# robot_secondaire.net
KiCad netlist of a schematic drawn in EAGLE
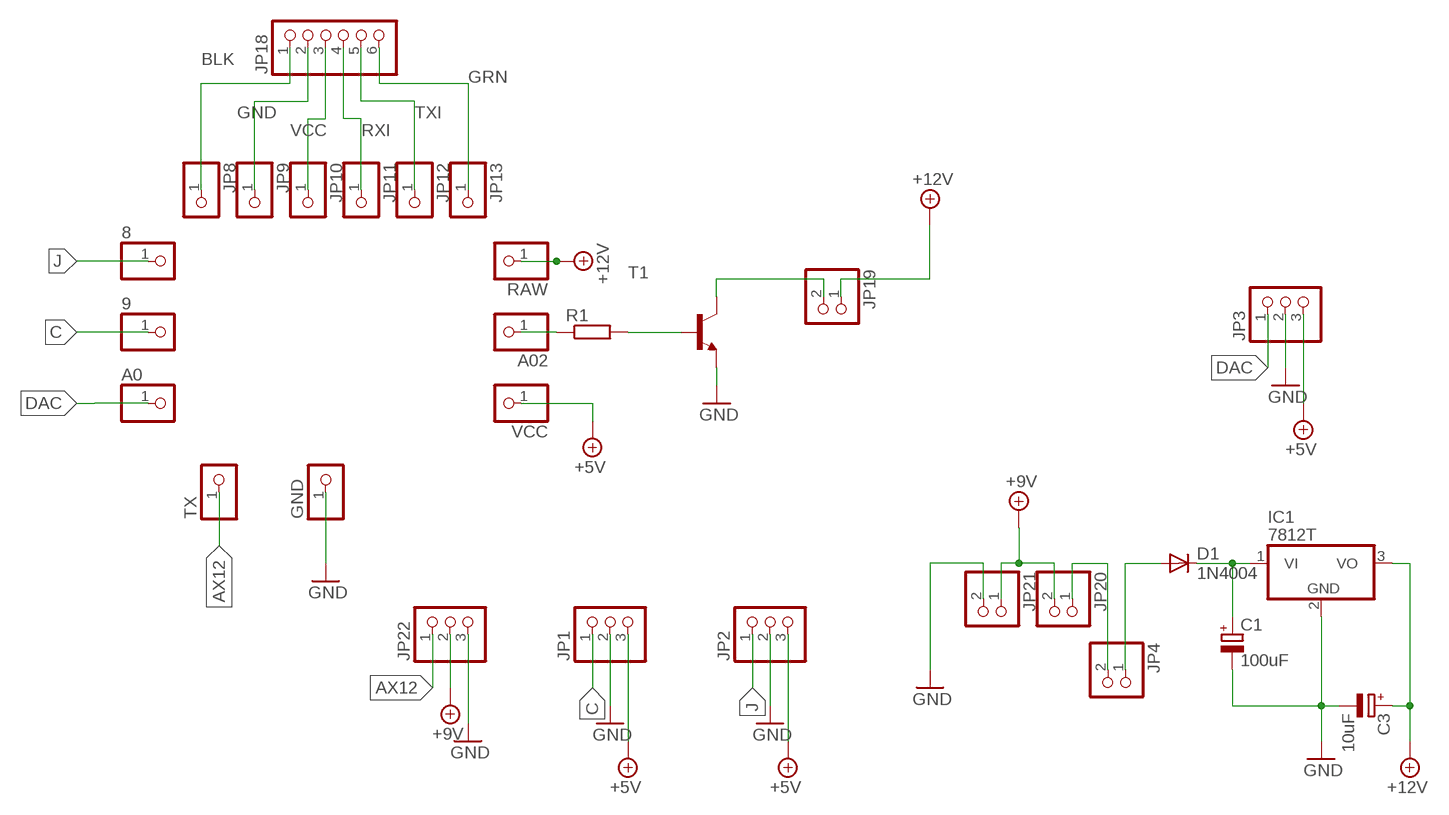
[diagram p0: schematic, sheet 1]

(export (version "E")
  (design (tool "Eeschema 10.0.6"))
  (components
    (comp (ref "8")
      (value "PINHD-1X1")
      (footprint "eagle-import:1X01")
      (libsource (lib "eagle-import") (part "PINHD-1X1"))
    )
    (comp (ref "9")
      (value "PINHD-1X1")
      (footprint "eagle-import:1X01")
      (libsource (lib "eagle-import") (part "PINHD-1X1"))
    )
    (comp (ref "A0")
      (value "PINHD-1X1")
      (footprint "eagle-import:1X01")
      (libsource (lib "eagle-import") (part "PINHD-1X1"))
    )
    (comp (ref "A02")
      (value "PINHD-1X1")
      (footprint "eagle-import:1X01")
      (libsource (lib "eagle-import") (part "PINHD-1X1"))
    )
    (comp (ref "C1")
      (value "100uF")
      (footprint "eagle-import:E3,5-10")
      (libsource (lib "eagle-import") (part "CPOL-EUE3.5-10"))
    )
    (comp (ref "C3")
      (value "10uF")
      (footprint "eagle-import:E2,5-6E")
      (libsource (lib "eagle-import") (part "CPOL-EUE2,5-6E"))
    )
    (comp (ref "D1")
      (value "1N4004")
      (footprint "eagle-import:DO41-10")
      (libsource (lib "eagle-import") (part "1N4004"))
    )
    (comp (ref "GND")
      (value "PINHD-1X1")
      (footprint "eagle-import:1X01")
      (libsource (lib "eagle-import") (part "PINHD-1X1"))
    )
    (comp (ref "IC1")
      (value "7812T")
      (footprint "eagle-import:TO220H")
      (libsource (lib "eagle-import") (part "78T12"))
    )
    (comp (ref "JP1")
      (value "PINHD-1X3")
      (footprint "eagle-import:1X03")
      (libsource (lib "eagle-import") (part "PINHD-1X3"))
    )
    (comp (ref "JP2")
      (value "PINHD-1X3")
      (footprint "eagle-import:1X03")
      (libsource (lib "eagle-import") (part "PINHD-1X3"))
    )
    (comp (ref "JP3")
      (value "PINHD-1X3")
      (footprint "eagle-import:1X03")
      (libsource (lib "eagle-import") (part "PINHD-1X3"))
    )
    (comp (ref "JP4")
      (value "PINHD-1X2")
      (footprint "eagle-import:1X02")
      (libsource (lib "eagle-import") (part "PINHD-1X2"))
    )
    (comp (ref "JP8")
      (value "PINHD-1X1")
      (footprint "eagle-import:1X01")
      (libsource (lib "eagle-import") (part "PINHD-1X1"))
    )
    (comp (ref "JP9")
      (value "PINHD-1X1")
      (footprint "eagle-import:1X01")
      (libsource (lib "eagle-import") (part "PINHD-1X1"))
    )
    (comp (ref "JP10")
      (value "PINHD-1X1")
      (footprint "eagle-import:1X01")
      (libsource (lib "eagle-import") (part "PINHD-1X1"))
    )
    (comp (ref "JP11")
      (value "PINHD-1X1")
      (footprint "eagle-import:1X01")
      (libsource (lib "eagle-import") (part "PINHD-1X1"))
    )
    (comp (ref "JP12")
      (value "PINHD-1X1")
      (footprint "eagle-import:1X01")
      (libsource (lib "eagle-import") (part "PINHD-1X1"))
    )
    (comp (ref "JP13")
      (value "PINHD-1X1")
      (footprint "eagle-import:1X01")
      (libsource (lib "eagle-import") (part "PINHD-1X1"))
    )
    (comp (ref "JP18")
      (value "PINHD-1X6")
      (footprint "eagle-import:1X06")
      (libsource (lib "eagle-import") (part "PINHD-1X6"))
    )
    (comp (ref "JP19")
      (value "PINHD-1X2")
      (footprint "eagle-import:1X02")
      (libsource (lib "eagle-import") (part "PINHD-1X2"))
    )
    (comp (ref "JP20")
      (value "PINHD-1X2")
      (footprint "eagle-import:1X02")
      (libsource (lib "eagle-import") (part "PINHD-1X2"))
    )
    (comp (ref "JP21")
      (value "PINHD-1X2")
      (footprint "eagle-import:1X02")
      (libsource (lib "eagle-import") (part "PINHD-1X2"))
    )
    (comp (ref "JP22")
      (value "PINHD-1X3")
      (footprint "eagle-import:1X03")
      (libsource (lib "eagle-import") (part "PINHD-1X3"))
    )
    (comp (ref "R1")
      (value "R-EU_0204/7")
      (footprint "eagle-import:0204_7")
      (libsource (lib "eagle-import") (part "R-EU_0204/7"))
    )
    (comp (ref "RAW")
      (value "PINHD-1X1")
      (footprint "eagle-import:1X01")
      (libsource (lib "eagle-import") (part "PINHD-1X1"))
    )
    (comp (ref "T1")
      (value "2N4124-NPN-TO92-CBE")
      (footprint "eagle-import:TO92-CBE")
      (libsource (lib "eagle-import") (part "-NPN-TO92-CBE2N4124"))
    )
    (comp (ref "TX")
      (value "PINHD-1X1")
      (footprint "eagle-import:1X01")
      (libsource (lib "eagle-import") (part "PINHD-1X1"))
    )
    (comp (ref "VCC")
      (value "PINHD-1X1")
      (footprint "eagle-import:1X01")
      (libsource (lib "eagle-import") (part "PINHD-1X1"))
    )
  )
  (nets
    (net (code "1") (name "+5V") (class "Default")
      (node (ref "JP1") (pin "3") (pinfunction "3_3") (pintype "passive"))
      (node (ref "JP2") (pin "3") (pinfunction "3_3") (pintype "passive"))
      (node (ref "JP3") (pin "3") (pinfunction "3_3") (pintype "passive"))
      (node (ref "VCC") (pin "1") (pinfunction "1_1") (pintype "passive"))
    )
    (net (code "2") (name "+9V") (class "Default")
      (node (ref "JP20") (pin "2") (pinfunction "2_2") (pintype "passive"))
      (node (ref "JP21") (pin "1") (pinfunction "1_1") (pintype "passive"))
      (node (ref "JP22") (pin "2") (pinfunction "2_2") (pintype "passive"))
    )
    (net (code "3") (name "+12V") (class "Default")
      (node (ref "C3") (pin "+") (pinfunction "+_+") (pintype "passive"))
      (node (ref "IC1") (pin "3") (pinfunction "VO_3") (pintype "passive"))
      (node (ref "JP19") (pin "1") (pinfunction "1_1") (pintype "passive"))
      (node (ref "RAW") (pin "1") (pinfunction "1_1") (pintype "passive"))
    )
    (net (code "4") (name "/BLK") (class "Default")
      (node (ref "JP18") (pin "1") (pinfunction "1_1") (pintype "passive"))
      (node (ref "JP8") (pin "1") (pinfunction "1_1") (pintype "passive"))
    )
    (net (code "5") (name "/GRN") (class "Default")
      (node (ref "JP13") (pin "1") (pinfunction "1_1") (pintype "passive"))
      (node (ref "JP18") (pin "6") (pinfunction "6_6") (pintype "passive"))
    )
    (net (code "6") (name "/RXI") (class "Default")
      (node (ref "JP11") (pin "1") (pinfunction "1_1") (pintype "passive"))
      (node (ref "JP18") (pin "4") (pinfunction "4_4") (pintype "passive"))
    )
    (net (code "7") (name "/TXI") (class "Default")
      (node (ref "JP12") (pin "1") (pinfunction "1_1") (pintype "passive"))
      (node (ref "JP18") (pin "5") (pinfunction "5_5") (pintype "passive"))
    )
    (net (code "8") (name "/VCC") (class "Default")
      (node (ref "JP10") (pin "1") (pinfunction "1_1") (pintype "passive"))
      (node (ref "JP18") (pin "3") (pinfunction "3_3") (pintype "passive"))
    )
    (net (code "9") (name "AX12") (class "Default")
      (node (ref "JP22") (pin "1") (pinfunction "1_1") (pintype "passive"))
      (node (ref "TX") (pin "1") (pinfunction "1_1") (pintype "passive"))
    )
    (net (code "10") (name "C") (class "Default")
      (node (ref "9") (pin "1") (pinfunction "1_1") (pintype "passive"))
      (node (ref "JP1") (pin "1") (pinfunction "1_1") (pintype "passive"))
    )
    (net (code "11") (name "DAC") (class "Default")
      (node (ref "A0") (pin "1") (pinfunction "1_1") (pintype "passive"))
      (node (ref "JP3") (pin "1") (pinfunction "1_1") (pintype "passive"))
    )
    (net (code "12") (name "GND") (class "Default")
      (node (ref "C1") (pin "-") (pinfunction "-_-") (pintype "passive"))
      (node (ref "C3") (pin "-") (pinfunction "-_-") (pintype "passive"))
      (node (ref "GND") (pin "1") (pinfunction "1_1") (pintype "passive"))
      (node (ref "IC1") (pin "2") (pinfunction "GND_2") (pintype "passive"))
      (node (ref "JP1") (pin "2") (pinfunction "2_2") (pintype "passive"))
      (node (ref "JP18") (pin "2") (pinfunction "2_2") (pintype "passive"))
      (node (ref "JP2") (pin "2") (pinfunction "2_2") (pintype "passive"))
      (node (ref "JP21") (pin "2") (pinfunction "2_2") (pintype "passive"))
      (node (ref "JP22") (pin "3") (pinfunction "3_3") (pintype "passive"))
      (node (ref "JP3") (pin "2") (pinfunction "2_2") (pintype "passive"))
      (node (ref "JP9") (pin "1") (pinfunction "1_1") (pintype "passive"))
      (node (ref "T1") (pin "E") (pinfunction "E_E") (pintype "passive"))
    )
    (net (code "13") (name "J") (class "Default")
      (node (ref "8") (pin "1") (pinfunction "1_1") (pintype "passive"))
      (node (ref "JP2") (pin "1") (pinfunction "1_1") (pintype "passive"))
    )
    (net (code "14") (name "Net-(A02-Pad1)") (class "Default")
      (node (ref "A02") (pin "1") (pinfunction "1_1") (pintype "passive"))
      (node (ref "R1") (pin "1") (pinfunction "1_1") (pintype "passive"))
    )
    (net (code "15") (name "Net-(D1-PadA)") (class "Default")
      (node (ref "D1") (pin "A") (pinfunction "A_A") (pintype "passive"))
      (node (ref "JP4") (pin "1") (pinfunction "1_1") (pintype "passive"))
    )
    (net (code "16") (name "Net-(IC1-VI)") (class "Default")
      (node (ref "C1") (pin "+") (pinfunction "+_+") (pintype "passive"))
      (node (ref "D1") (pin "C") (pinfunction "C_C") (pintype "passive"))
      (node (ref "IC1") (pin "1") (pinfunction "VI_1") (pintype "input"))
    )
    (net (code "17") (name "Net-(JP19-Pad2)") (class "Default")
      (node (ref "JP19") (pin "2") (pinfunction "2_2") (pintype "passive"))
      (node (ref "T1") (pin "C") (pinfunction "C_C") (pintype "passive"))
    )
    (net (code "18") (name "Net-(JP20-Pad1)") (class "Default")
      (node (ref "JP20") (pin "1") (pinfunction "1_1") (pintype "passive"))
      (node (ref "JP4") (pin "2") (pinfunction "2_2") (pintype "passive"))
    )
    (net (code "19") (name "Net-(R1-Pad2)") (class "Default")
      (node (ref "R1") (pin "2") (pinfunction "2_2") (pintype "passive"))
      (node (ref "T1") (pin "B") (pinfunction "B_B") (pintype "passive"))
    )
  )
)
